# CAPT-A1-01_Cap_Touch_Slider_FeatherWing.net
KiCad netlist of a schematic drawn in EAGLE
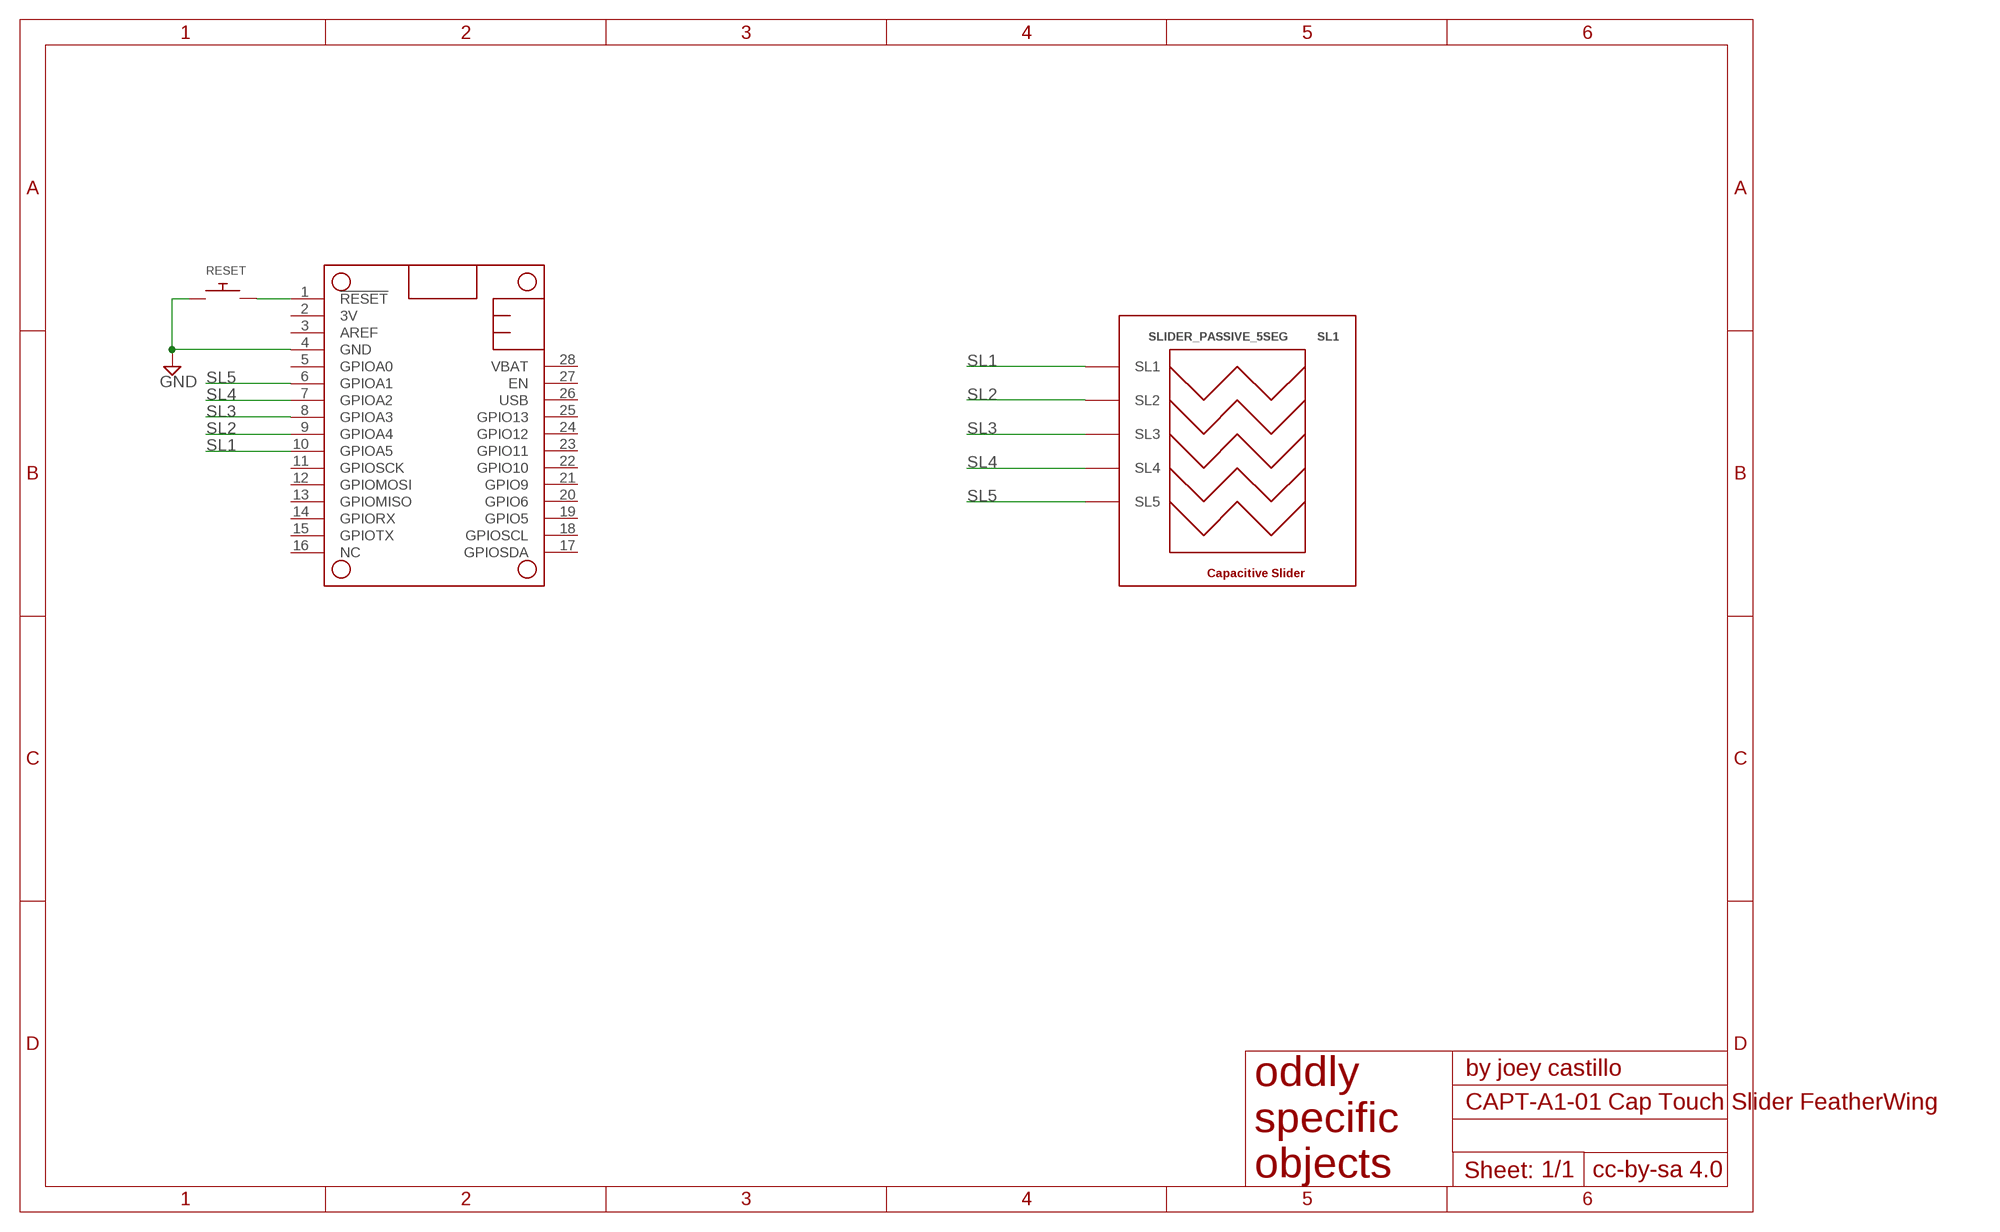
[diagram p0: schematic, sheet 1]

(export (version "E")
  (design (tool "Eeschema 10.0.6"))
  (components
    (comp (ref "MS1")
      (value "FEATHERWING")
      (footprint "eagle-import:FEATHERWING")
      (libsource (lib "eagle-import") (part "FEATHERWING"))
    )
    (comp (ref "RESET")
      (value "SPST_TACTILE_SWITCHRA-THRU")
      (footprint "eagle-import:MJTP1117")
      (libsource (lib "eagle-import") (part "SPST_TACTILE_SWITCHRA-THRU"))
    )
    (comp (ref "SL1")
      (value "SLIDER_PASSIVE_5SEG")
      (footprint "eagle-import:SLIDER_PASSIVE_5SEG_12MM")
      (libsource (lib "eagle-import") (part "SLIDER_PASSIVE_5SEG"))
    )
  )
  (nets
    (net (code "1") (name "/3V") (class "Default")
      (node (ref "MS1") (pin "2") (pinfunction "3V_2") (pintype "power_in"))
    )
    (net (code "2") (name "/SL1") (class "Default")
      (node (ref "MS1") (pin "10") (pinfunction "GPIOA5_10") (pintype "bidirectional"))
      (node (ref "SL1") (pin "SL1") (pinfunction "SL1_SL1") (pintype "passive"))
    )
    (net (code "3") (name "/SL2") (class "Default")
      (node (ref "MS1") (pin "9") (pinfunction "GPIOA4_9") (pintype "bidirectional"))
      (node (ref "SL1") (pin "SL2") (pinfunction "SL2_SL2") (pintype "passive"))
    )
    (net (code "4") (name "/SL3") (class "Default")
      (node (ref "MS1") (pin "8") (pinfunction "GPIOA3_8") (pintype "bidirectional"))
      (node (ref "SL1") (pin "SL3") (pinfunction "SL3_SL3") (pintype "passive"))
    )
    (net (code "5") (name "/SL4") (class "Default")
      (node (ref "MS1") (pin "7") (pinfunction "GPIOA2_7") (pintype "bidirectional"))
      (node (ref "SL1") (pin "SL4") (pinfunction "SL4_SL4") (pintype "passive"))
    )
    (net (code "6") (name "/SL5") (class "Default")
      (node (ref "MS1") (pin "6") (pinfunction "GPIOA1_6") (pintype "bidirectional"))
      (node (ref "SL1") (pin "SL5") (pinfunction "SL5_SL5") (pintype "passive"))
    )
    (net (code "7") (name "/USB") (class "Default")
      (node (ref "MS1") (pin "26") (pinfunction "USB_26") (pintype "power_in"))
    )
    (net (code "8") (name "/VBAT") (class "Default")
      (node (ref "MS1") (pin "28") (pinfunction "VBAT_28") (pintype "power_in"))
    )
    (net (code "9") (name "GND") (class "Default")
      (node (ref "MS1") (pin "4") (pinfunction "GND_4") (pintype "power_in"))
      (node (ref "RESET") (pin "P$1") (pinfunction "P$1_P$1") (pintype "passive"))
    )
    (net (code "10") (name "Net-(MS1-~{RESET})") (class "Default")
      (node (ref "MS1") (pin "1") (pinfunction "~{RESET}_1") (pintype "input"))
      (node (ref "RESET") (pin "P$2") (pinfunction "P$2_P$2") (pintype "passive"))
    )
    (net (code "11") (name "unconnected-(MS1-AREF-Pad3)") (class "Default")
      (node (ref "MS1") (pin "3") (pinfunction "AREF_3") (pintype "passive"))
    )
    (net (code "12") (name "unconnected-(MS1-EN-Pad27)") (class "Default")
      (node (ref "MS1") (pin "27") (pinfunction "EN_27") (pintype "passive"))
    )
    (net (code "13") (name "unconnected-(MS1-GPIO5-Pad19)") (class "Default")
      (node (ref "MS1") (pin "19") (pinfunction "GPIO5_19") (pintype "bidirectional"))
    )
    (net (code "14") (name "unconnected-(MS1-GPIO6-Pad20)") (class "Default")
      (node (ref "MS1") (pin "20") (pinfunction "GPIO6_20") (pintype "bidirectional"))
    )
    (net (code "15") (name "unconnected-(MS1-GPIO9-Pad21)") (class "Default")
      (node (ref "MS1") (pin "21") (pinfunction "GPIO9_21") (pintype "bidirectional"))
    )
    (net (code "16") (name "unconnected-(MS1-GPIO10-Pad22)") (class "Default")
      (node (ref "MS1") (pin "22") (pinfunction "GPIO10_22") (pintype "bidirectional"))
    )
    (net (code "17") (name "unconnected-(MS1-GPIO11-Pad23)") (class "Default")
      (node (ref "MS1") (pin "23") (pinfunction "GPIO11_23") (pintype "bidirectional"))
    )
    (net (code "18") (name "unconnected-(MS1-GPIO12-Pad24)") (class "Default")
      (node (ref "MS1") (pin "24") (pinfunction "GPIO12_24") (pintype "bidirectional"))
    )
    (net (code "19") (name "unconnected-(MS1-GPIO13-Pad25)") (class "Default")
      (node (ref "MS1") (pin "25") (pinfunction "GPIO13_25") (pintype "bidirectional"))
    )
    (net (code "20") (name "unconnected-(MS1-GPIOA0-Pad5)") (class "Default")
      (node (ref "MS1") (pin "5") (pinfunction "GPIOA0_5") (pintype "bidirectional"))
    )
    (net (code "21") (name "unconnected-(MS1-GPIOMISO-Pad13)") (class "Default")
      (node (ref "MS1") (pin "13") (pinfunction "GPIOMISO_13") (pintype "bidirectional"))
    )
    (net (code "22") (name "unconnected-(MS1-GPIOMOSI-Pad12)") (class "Default")
      (node (ref "MS1") (pin "12") (pinfunction "GPIOMOSI_12") (pintype "bidirectional"))
    )
    (net (code "23") (name "unconnected-(MS1-GPIORX-Pad14)") (class "Default")
      (node (ref "MS1") (pin "14") (pinfunction "GPIORX_14") (pintype "bidirectional"))
    )
    (net (code "24") (name "unconnected-(MS1-GPIOSCK-Pad11)") (class "Default")
      (node (ref "MS1") (pin "11") (pinfunction "GPIOSCK_11") (pintype "bidirectional"))
    )
    (net (code "25") (name "unconnected-(MS1-GPIOSCL-Pad18)") (class "Default")
      (node (ref "MS1") (pin "18") (pinfunction "GPIOSCL_18") (pintype "bidirectional"))
    )
    (net (code "26") (name "unconnected-(MS1-GPIOSDA-Pad17)") (class "Default")
      (node (ref "MS1") (pin "17") (pinfunction "GPIOSDA_17") (pintype "bidirectional"))
    )
    (net (code "27") (name "unconnected-(MS1-GPIOTX-Pad15)") (class "Default")
      (node (ref "MS1") (pin "15") (pinfunction "GPIOTX_15") (pintype "bidirectional"))
    )
    (net (code "28") (name "unconnected-(MS1-NC-Pad16)") (class "Default")
      (node (ref "MS1") (pin "16") (pinfunction "NC_16") (pintype "passive"))
    )
  )
)
